# PWR_Buck_P2V5_8A.net
KiCad netlist of a schematic drawn in Altium Designer
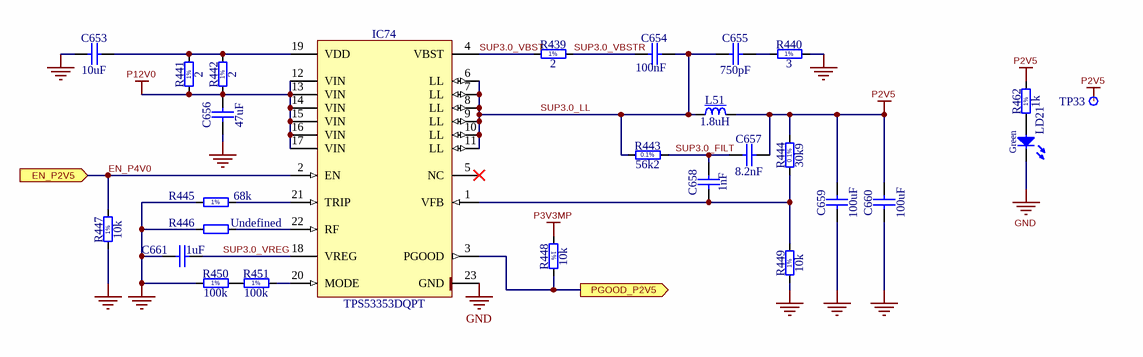
[diagram p0: PWR_Buck_P2V5_8A.SchDoc]

(export (version "E")
  (design (tool "Eeschema 10.0.6"))
  (components
    (comp (ref "C653")
      (value "10uF")
      (footprint "CAPC3216X180N")
      (description "Non-polarised capacitor")
      (fields
        (field (name "MANUFACTURER PART NUMBER") "CC1206_10uF_25V_10%_X7R")
        (field (name "MANUFACTURER") "GENERIC")
        (field (name "AUTHOR") "CERN DEM JLC")
      )
      (libsource (lib "Capacitors") (part "Capacitor - non polarized"))
    )
    (comp (ref "C654")
      (value "100nF")
      (footprint "CAPC1005X55N")
      (description "Non-polarised capacitor")
      (fields
        (field (name "MANUFACTURER PART NUMBER") "CC0402_100NF_16V_10%_X5R")
        (field (name "MANUFACTURER") "GENERIC")
        (field (name "AUTHOR") "CERN DEM JLC")
      )
      (libsource (lib "Capacitors") (part "Capacitor - non polarized"))
    )
    (comp (ref "C655")
      (value "750pF")
      (footprint "CAPC1608X87N")
      (description "Non-polarised capacitor")
      (fields
        (field (name "PART NUMBER") "CC0603_750PF_50V_5%_C0G")
        (field (name "VOLTAGE") "50V")
        (field (name "AUTHOR") "CERN DEM JLC")
      )
      (libsource (lib "Capacitors") (part "Capacitor - non polarized"))
    )
    (comp (ref "C656")
      (value "47uF")
      (footprint "CAPC3225X270N")
      (description "Non-polarised capacitor")
      (fields
        (field (name "PART NUMBER") "CC1210_47UF_16V_20%_X5R")
        (field (name "VOLTAGE") "16V")
        (field (name "AUTHOR") "CERN DEM MR")
      )
      (libsource (lib "Capacitors") (part "Capacitor - non polarized"))
    )
    (comp (ref "C657")
      (value "8.2nF")
      (footprint "CAPC1608X87N")
      (description "Non-polarised capacitor")
      (fields
        (field (name "PART NUMBER") "CC0603_8.2NF_50V_5%_X7R")
        (field (name "VOLTAGE") "50V")
        (field (name "AUTHOR") "CERN DEM JLC")
      )
      (libsource (lib "Capacitors") (part "Capacitor - non polarized"))
    )
    (comp (ref "C658")
      (value "1nF")
      (footprint "CAPC1005X55N")
      (description "Non-polarised capacitor")
      (fields
        (field (name "MANUFACTURER PART NUMBER") "CC0402_1NF_50V_10%_X7R")
        (field (name "MANUFACTURER") "GENERIC")
        (field (name "AUTHOR") "CERN DEM JLC")
      )
      (libsource (lib "Capacitors") (part "Capacitor - non polarized"))
    )
    (comp (ref "C659")
      (value "100uF")
      (footprint "CAPC3216X180N")
      (description "Non-polarised capacitor")
      (fields
        (field (name "MANUFACTURER PART NUMBER") "CC1206_100UF_6.3V_20%_X5R")
        (field (name "MANUFACTURER") "GENERIC")
        (field (name "AUTHOR") "CERN DEM JLC")
      )
      (libsource (lib "Capacitors") (part "Capacitor - non polarized"))
    )
    (comp (ref "C660")
      (value "100uF")
      (footprint "CAPC3216X180N")
      (description "Non-polarised capacitor")
      (fields
        (field (name "MANUFACTURER PART NUMBER") "CC1206_100UF_6.3V_20%_X5R")
        (field (name "MANUFACTURER") "GENERIC")
        (field (name "AUTHOR") "CERN DEM JLC")
      )
      (libsource (lib "Capacitors") (part "Capacitor - non polarized"))
    )
    (comp (ref "C661")
      (value "1uF")
      (footprint "CAPC1608X87N")
      (description "Non-polarised capacitor")
      (fields
        (field (name "MANUFACTURER PART NUMBER") "CC0603_1UF_25V_10%_X7R")
        (field (name "MANUFACTURER") "GENERIC")
        (field (name "AUTHOR") "CERN DEM JLC")
      )
      (libsource (lib "Capacitors") (part "Capacitor - non polarized"))
    )
    (comp (ref "IC74")
      (value "TPS53353DQPT")
      (footprint "SON50P500X600X150-23N-R334X557")
      (description "1.5V to 15V Input (4.5V to 25V Bias), 20A Synchronous Buck SWIFT™ Converter with Eco-mode™")
      (fields (field (name "MANUFACTURER") "TEXAS INSTRUMENTS"))
      (libsource (lib "TP_LIB") (part "TPS53353DQPT"))
    )
    (comp (ref "L51")
      (value "1.8uH")
      (footprint "IND_COILCRAFT_XAL7070")
      (description "Inductor With Core")
      (fields
        (field (name "PART NUMBER") "IND_1.8UH_20%_COILCRAFT_XAL7070")
        (field (name "POWER") "15.8A")
        (field (name "AUTHOR") "CERN DEM JLC")
      )
      (libsource (lib "Inductors & Transformers") (part "Inductor With Magnetic core"))
    )
    (comp (ref "LD21")
      (value "Green")
      (footprint "LED_OSRAM_LGL29K")
      (description "LED Green 1C 2A")
      (fields
        (field (name "MANUFACTURER PART NUMBER") "LG L29K-G2J1-24-Z")
        (field (name "MANUFACTURER") "OSRAM")
        (field (name "AUTHOR") "CERN DEM JLC")
      )
      (libsource (lib "ICs And Semiconductors") (part "LED Green 1C 2A"))
    )
    (comp (ref "R439")
      (value "2")
      (footprint "RESC1608X55N")
      (description "Resistor - 1%")
      (fields
        (field (name "MANUFACTURER PART NUMBER") "R0603_2R_1%_0.1W_200PPM")
        (field (name "MANUFACTURER") "GENERIC")
        (field (name "AUTHOR") "CERN DEM JLC")
      )
      (libsource (lib "Resistors") (part "Resistor - 1%"))
    )
    (comp (ref "R440")
      (value "3")
      (footprint "RESC3216X65N")
      (description "Resistor - 1%")
      (fields
        (field (name "MANUFACTURER PART NUMBER") "R1206_3R_1%_0.25W_200PPM")
        (field (name "MANUFACTURER") "GENERIC")
        (field (name "AUTHOR") "CERN DEM JLC")
      )
      (libsource (lib "Resistors") (part "Resistor - 1%"))
    )
    (comp (ref "R441")
      (value "2")
      (footprint "RESC1608X55N")
      (description "Resistor - 1%")
      (fields
        (field (name "MANUFACTURER PART NUMBER") "R0603_2R_1%_0.1W_200PPM")
        (field (name "MANUFACTURER") "GENERIC")
        (field (name "AUTHOR") "CERN DEM JLC")
      )
      (libsource (lib "Resistors") (part "Resistor - 1%"))
    )
    (comp (ref "R442")
      (value "2")
      (footprint "RESC1608X55N")
      (description "Resistor - 1%")
      (fields
        (field (name "MANUFACTURER PART NUMBER") "R0603_2R_1%_0.1W_200PPM")
        (field (name "MANUFACTURER") "GENERIC")
        (field (name "AUTHOR") "CERN DEM JLC")
      )
      (libsource (lib "Resistors") (part "Resistor - 1%"))
    )
    (comp (ref "R443")
      (value "56k2")
      (footprint "RESC1608X55N")
      (description "Resistor - 0.1%")
      (fields
        (field (name "PART NUMBER") "R0603_56K2_0.1%_0.063W_10PPM")
        (field (name "POWER") "0.063W")
        (field (name "AUTHOR") "CERN DEM JLC")
      )
      (libsource (lib "Resistors") (part "Resistor - 0.1%"))
    )
    (comp (ref "R444")
      (value "30k9")
      (footprint "RESC1608X55N")
      (description "Resistor - 0.1%")
      (fields
        (field (name "PART NUMBER") "R0603_30K9_0.1%_0.063W_10PPM")
        (field (name "POWER") "0.063W")
        (field (name "AUTHOR") "CERN DEM JLC")
      )
      (libsource (lib "Resistors") (part "Resistor - 0.1%"))
    )
    (comp (ref "R445")
      (value "68k")
      (footprint "RESC1005X40N")
      (description "Resistor - 1%")
      (fields
        (field (name "PART NUMBER") "R0402_68K_1%_0.0625W_100PPM")
        (field (name "POWER") "0.0625W")
        (field (name "AUTHOR") "CERN DEM JLC")
      )
      (libsource (lib "Resistors") (part "Resistor - 1%"))
    )
    (comp (ref "R446")
      (value "Undefined")
      (footprint "RESC1005X40N")
      (description "Resistor")
      (fields
        (field (name "MANUFACTURER PART NUMBER") "R0402_NO-VALUE")
        (field (name "AUTHOR") "CERN DEM JLC")
      )
      (libsource (lib "Resistors") (part "Resistor"))
    )
    (comp (ref "R447")
      (value "10k")
      (footprint "RESC1005X40N")
      (description "Resistor - 1%")
      (fields
        (field (name "MANUFACTURER PART NUMBER") "R0402_10K_1%_0.0625W_100PPM")
        (field (name "MANUFACTURER") "GENERIC")
        (field (name "AUTHOR") "CERN DEM JLC")
      )
      (libsource (lib "Resistors") (part "Resistor - 1%"))
    )
    (comp (ref "R448")
      (value "10k")
      (footprint "RESC1005X40N")
      (description "Resistor - 1%")
      (fields
        (field (name "MANUFACTURER PART NUMBER") "R0402_10K_1%_0.0625W_100PPM")
        (field (name "MANUFACTURER") "GENERIC")
        (field (name "AUTHOR") "CERN DEM JLC")
      )
      (libsource (lib "Resistors") (part "Resistor - 1%"))
    )
    (comp (ref "R449")
      (value "10k")
      (footprint "RESC1005X40N")
      (description "Resistor - 1%")
      (fields
        (field (name "PART NUMBER") "R0402_10K_1%_0.0625W_100PPM")
        (field (name "POWER") "0.0625W")
        (field (name "AUTHOR") "CERN DEM JLC")
      )
      (libsource (lib "Resistors") (part "Resistor - 1%"))
    )
    (comp (ref "R450")
      (value "100k")
      (footprint "RESC1005X40N")
      (description "Resistor - 1%")
      (fields
        (field (name "MANUFACTURER PART NUMBER") "R0402_100K_1%_0.0625W_100PPM")
        (field (name "MANUFACTURER") "GENERIC")
        (field (name "AUTHOR") "CERN DEM JLC")
      )
      (libsource (lib "Resistors") (part "Resistor - 1%"))
    )
    (comp (ref "R451")
      (value "100k")
      (footprint "RESC1005X40N")
      (description "Resistor - 1%")
      (fields
        (field (name "MANUFACTURER PART NUMBER") "R0402_100K_1%_0.0625W_100PPM")
        (field (name "MANUFACTURER") "GENERIC")
        (field (name "AUTHOR") "CERN DEM JLC")
      )
      (libsource (lib "Resistors") (part "Resistor - 1%"))
    )
    (comp (ref "R462")
      (value "1k")
      (footprint "RESC1005X40N")
      (description "Resistor - 1%")
      (fields
        (field (name "MANUFACTURER PART NUMBER") "R0402_1K_1%_0.0625W_100PPM")
        (field (name "MANUFACTURER") "GENERIC")
        (field (name "AUTHOR") "CERN DEM JLC")
      )
      (libsource (lib "Resistors") (part "Resistor - 1%"))
    )
    (comp (ref "TP33")
      (value "Test Point")
      (footprint "TPS127")
      (fields (field (name "PART NUMBER") "SMD_PAD_1.27X1.27MM") (field (name "AUTHOR") "CERN DEM JLC"))
      (libsource (lib "Eletro-mechanical") (part "Test Point"))
    )
  )
  (nets
    (net (code "1") (name "/EN_P4V0") (class "Default")
      (node (ref "IC74") (pin "2") (pinfunction "EN_2") (pintype "input"))
      (node (ref "R447") (pin "1") (pinfunction "1_1") (pintype "passive"))
    )
    (net (code "2") (name "/PGOOD_P2V5") (class "Default")
      (node (ref "IC74") (pin "3") (pinfunction "PGOOD_3") (pintype "output"))
      (node (ref "R448") (pin "1") (pinfunction "1_1") (pintype "passive"))
    )
    (net (code "3") (name "/SUP3.0_FILT") (class "Default")
      (node (ref "C657") (pin "1") (pinfunction "1_1") (pintype "passive"))
      (node (ref "C658") (pin "2") (pinfunction "2_2") (pintype "passive"))
      (node (ref "R443") (pin "2") (pinfunction "2_2") (pintype "passive"))
    )
    (net (code "4") (name "/SUP3.0_LL") (class "Default")
      (node (ref "C654") (pin "2") (pinfunction "2_2") (pintype "passive"))
      (node (ref "C655") (pin "1") (pinfunction "1_1") (pintype "passive"))
      (node (ref "IC74") (pin "10") (pinfunction "LL_10") (pintype "bidirectional"))
      (node (ref "IC74") (pin "11") (pinfunction "LL_11") (pintype "bidirectional"))
      (node (ref "IC74") (pin "6") (pinfunction "LL_6") (pintype "bidirectional"))
      (node (ref "IC74") (pin "7") (pinfunction "LL_7") (pintype "bidirectional"))
      (node (ref "IC74") (pin "8") (pinfunction "LL_8") (pintype "bidirectional"))
      (node (ref "IC74") (pin "9") (pinfunction "LL_9") (pintype "bidirectional"))
      (node (ref "L51") (pin "1") (pinfunction "1_1") (pintype "passive"))
      (node (ref "R443") (pin "1") (pinfunction "1_1") (pintype "passive"))
    )
    (net (code "5") (name "/SUP3.0_VBST") (class "Default")
      (node (ref "IC74") (pin "4") (pinfunction "VBST_4") (pintype "power_in"))
      (node (ref "R439") (pin "1") (pinfunction "1_1") (pintype "passive"))
    )
    (net (code "6") (name "/SUP3.0_VBSTR") (class "Default")
      (node (ref "C654") (pin "1") (pinfunction "1_1") (pintype "passive"))
      (node (ref "R439") (pin "2") (pinfunction "2_2") (pintype "passive"))
    )
    (net (code "7") (name "/SUP3.0_VREG") (class "Default")
      (node (ref "C661") (pin "1") (pinfunction "1_1") (pintype "passive"))
      (node (ref "IC74") (pin "18") (pinfunction "VREG_18") (pintype "power_in"))
    )
    (net (code "8") (name "GND") (class "Default")
      (node (ref "C653") (pin "2") (pinfunction "2_2") (pintype "passive"))
      (node (ref "C656") (pin "1") (pinfunction "1_1") (pintype "passive"))
      (node (ref "C659") (pin "1") (pinfunction "1_1") (pintype "passive"))
      (node (ref "C660") (pin "1") (pinfunction "1_1") (pintype "passive"))
      (node (ref "C661") (pin "2") (pinfunction "2_2") (pintype "passive"))
      (node (ref "IC74") (pin "23") (pinfunction "GND_23") (pintype "power_in"))
      (node (ref "LD21") (pin "1") (pinfunction "C_1") (pintype "passive"))
      (node (ref "R440") (pin "2") (pinfunction "2_2") (pintype "passive"))
      (node (ref "R445") (pin "1") (pinfunction "1_1") (pintype "passive"))
      (node (ref "R446") (pin "2") (pinfunction "2_2") (pintype "passive"))
      (node (ref "R447") (pin "2") (pinfunction "2_2") (pintype "passive"))
      (node (ref "R449") (pin "1") (pinfunction "1_1") (pintype "passive"))
      (node (ref "R450") (pin "1") (pinfunction "1_1") (pintype "passive"))
    )
    (net (code "9") (name "Net-(C655-Pad2)") (class "Default")
      (node (ref "C655") (pin "2") (pinfunction "2_2") (pintype "passive"))
      (node (ref "R440") (pin "1") (pinfunction "1_1") (pintype "passive"))
    )
    (net (code "10") (name "Net-(IC74-MODE)") (class "Default")
      (node (ref "IC74") (pin "20") (pinfunction "MODE_20") (pintype "input"))
      (node (ref "R451") (pin "2") (pinfunction "2_2") (pintype "passive"))
    )
    (net (code "11") (name "Net-(IC74-RF)") (class "Default")
      (node (ref "IC74") (pin "22") (pinfunction "RF_22") (pintype "input"))
      (node (ref "R446") (pin "1") (pinfunction "1_1") (pintype "passive"))
    )
    (net (code "12") (name "Net-(IC74-TRIP)") (class "Default")
      (node (ref "IC74") (pin "21") (pinfunction "TRIP_21") (pintype "input"))
      (node (ref "R445") (pin "2") (pinfunction "2_2") (pintype "passive"))
    )
    (net (code "13") (name "Net-(IC74-VDD)") (class "Default")
      (node (ref "C653") (pin "1") (pinfunction "1_1") (pintype "passive"))
      (node (ref "IC74") (pin "19") (pinfunction "VDD_19") (pintype "power_in"))
      (node (ref "R441") (pin "2") (pinfunction "2_2") (pintype "passive"))
      (node (ref "R442") (pin "2") (pinfunction "2_2") (pintype "passive"))
    )
    (net (code "14") (name "Net-(IC74-VFB)") (class "Default")
      (node (ref "C658") (pin "1") (pinfunction "1_1") (pintype "passive"))
      (node (ref "IC74") (pin "1") (pinfunction "VFB_1") (pintype "input"))
      (node (ref "R444") (pin "1") (pinfunction "1_1") (pintype "passive"))
      (node (ref "R449") (pin "2") (pinfunction "2_2") (pintype "passive"))
    )
    (net (code "15") (name "Net-(LD21-A)") (class "Default")
      (node (ref "LD21") (pin "2") (pinfunction "A_2") (pintype "passive"))
      (node (ref "R462") (pin "1") (pinfunction "1_1") (pintype "passive"))
    )
    (net (code "16") (name "Net-(R450-Pad2)") (class "Default")
      (node (ref "R450") (pin "2") (pinfunction "2_2") (pintype "passive"))
      (node (ref "R451") (pin "1") (pinfunction "1_1") (pintype "passive"))
    )
    (net (code "17") (name "P2V5") (class "Default")
      (node (ref "C657") (pin "2") (pinfunction "2_2") (pintype "passive"))
      (node (ref "C659") (pin "2") (pinfunction "2_2") (pintype "passive"))
      (node (ref "C660") (pin "2") (pinfunction "2_2") (pintype "passive"))
      (node (ref "L51") (pin "2") (pinfunction "2_2") (pintype "passive"))
      (node (ref "R444") (pin "2") (pinfunction "2_2") (pintype "passive"))
      (node (ref "R462") (pin "2") (pinfunction "2_2") (pintype "passive"))
      (node (ref "TP33") (pin "1") (pinfunction "1_1") (pintype "bidirectional"))
    )
    (net (code "18") (name "P3V3MP") (class "Default")
      (node (ref "R448") (pin "2") (pinfunction "2_2") (pintype "passive"))
    )
    (net (code "19") (name "P12V0") (class "Default")
      (node (ref "C656") (pin "2") (pinfunction "2_2") (pintype "passive"))
      (node (ref "IC74") (pin "12") (pinfunction "VIN_12") (pintype "power_in"))
      (node (ref "IC74") (pin "13") (pinfunction "VIN_13") (pintype "power_in"))
      (node (ref "IC74") (pin "14") (pinfunction "VIN_14") (pintype "power_in"))
      (node (ref "IC74") (pin "15") (pinfunction "VIN_15") (pintype "power_in"))
      (node (ref "IC74") (pin "16") (pinfunction "VIN_16") (pintype "power_in"))
      (node (ref "IC74") (pin "17") (pinfunction "VIN_17") (pintype "power_in"))
      (node (ref "R441") (pin "1") (pinfunction "1_1") (pintype "passive"))
      (node (ref "R442") (pin "1") (pinfunction "1_1") (pintype "passive"))
    )
    (net (code "20") (name "unconnected-(IC74-NC-Pad5)") (class "Default")
      (node (ref "IC74") (pin "5") (pinfunction "NC_5") (pintype "passive+no_connect"))
    )
  )
)
